# SuperScreen.net
KiCad netlist of a schematic drawn in EAGLE
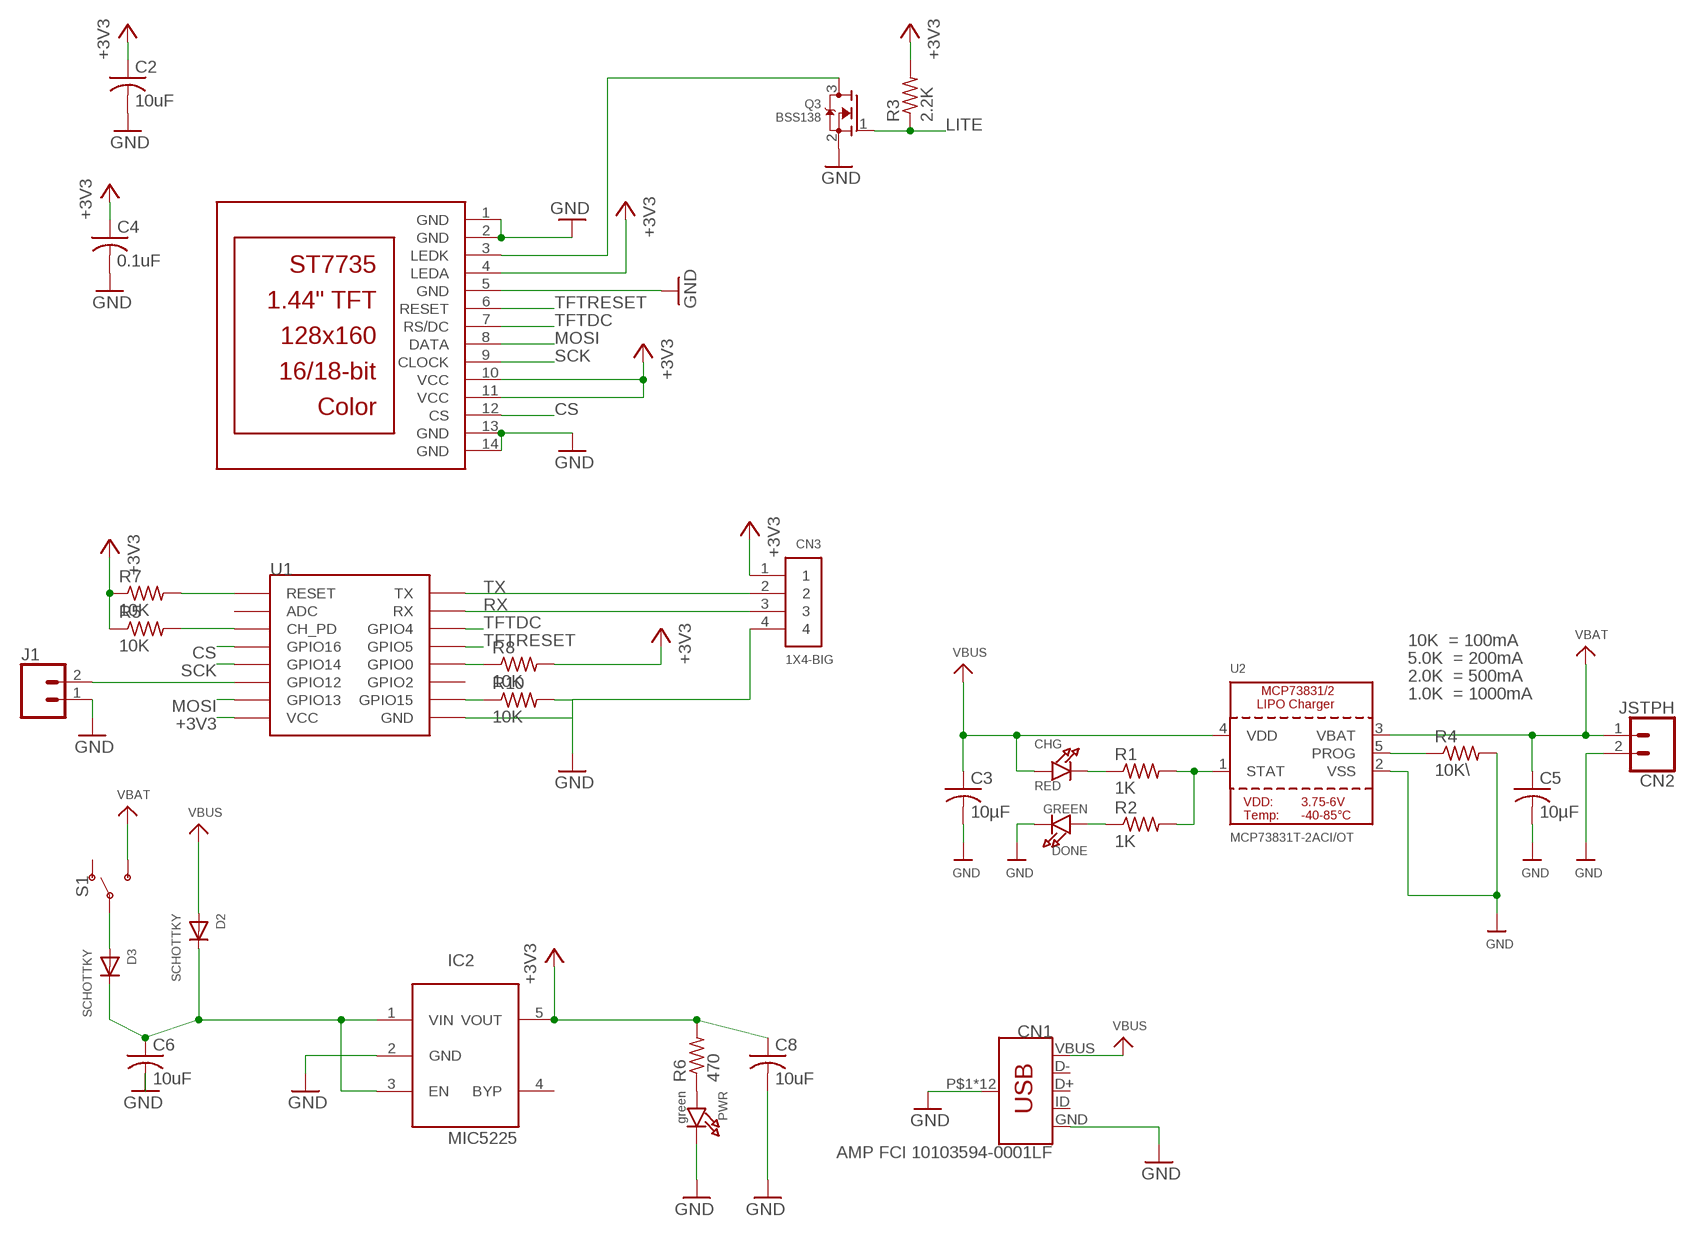
[diagram p0: schematic, sheet 1]

(export (version "E")
  (design (tool "Eeschema 10.0.6"))
  (components
    (comp (ref "C2")
      (value "10uF")
      (footprint "eagle-import:C0805")
      (libsource (lib "eagle-import") (part "C-USC0805"))
    )
    (comp (ref "C3")
      (value "10µF")
      (footprint "eagle-import:C0805")
      (libsource (lib "eagle-import") (part "C-USC0805"))
    )
    (comp (ref "C4")
      (value "0.1uF")
      (footprint "eagle-import:C0805")
      (libsource (lib "eagle-import") (part "C-USC0805"))
    )
    (comp (ref "C5")
      (value "10µF")
      (footprint "eagle-import:C0805")
      (libsource (lib "eagle-import") (part "C-USC0805"))
    )
    (comp (ref "C6")
      (value "10uF")
      (footprint "eagle-import:C0805")
      (libsource (lib "eagle-import") (part "C-USC0805"))
    )
    (comp (ref "C8")
      (value "10uF")
      (footprint "eagle-import:C0805")
      (libsource (lib "eagle-import") (part "C-USC0805"))
    )
    (comp (ref "CHG")
      (value "RED")
      (footprint "eagle-import:CHIPLED_0805_NOOUTLINE")
      (libsource (lib "eagle-import") (part "LED0805_NOOUTLINE"))
    )
    (comp (ref "CN1")
      (value "AMP FCI 10103594-0001LF")
      (footprint "eagle-import:USB-MICROB-PTH")
      (libsource (lib "eagle-import") (part "USB_MICRO-B_HALF_PTH"))
    )
    (comp (ref "CN2")
      (value "JSTPH")
      (footprint "eagle-import:1X02")
      (libsource (lib "eagle-import") (part "CONN_02"))
    )
    (comp (ref "CN3")
      (value "1X4-BIG")
      (footprint "eagle-import:1X04-BIG")
      (libsource (lib "eagle-import") (part "1X4-BIG"))
    )
    (comp (ref "D2")
      (value "SCHOTTKY")
      (footprint "eagle-import:SOD-123FL")
      (libsource (lib "eagle-import") (part "DIODE_SOD-123FL"))
    )
    (comp (ref "D3")
      (value "SCHOTTKY")
      (footprint "eagle-import:SOD-123FL")
      (libsource (lib "eagle-import") (part "DIODE_SOD-123FL"))
    )
    (comp (ref "DONE")
      (value "GREEN")
      (footprint "eagle-import:CHIPLED_0805_NOOUTLINE")
      (libsource (lib "eagle-import") (part "LED0805_NOOUTLINE"))
    )
    (comp (ref "IC2")
      (value "MIC5225")
      (footprint "eagle-import:SOT23-5L")
      (libsource (lib "eagle-import") (part "LP298XS"))
    )
    (comp (ref "J1")
      (value "CONN_02")
      (footprint "eagle-import:1X02")
      (libsource (lib "eagle-import") (part "CONN_02"))
    )
    (comp (ref "PWR")
      (value "green")
      (footprint "eagle-import:CHIPLED_0805_NOOUTLINE")
      (libsource (lib "eagle-import") (part "LED0805_NOOUTLINE"))
    )
    (comp (ref "Q3")
      (value "BSS138")
      (footprint "eagle-import:SOT23-WIDE")
      (libsource (lib "eagle-import") (part "MOSFET-NWIDE"))
    )
    (comp (ref "R1")
      (value "1K")
      (footprint "eagle-import:R0805")
      (libsource (lib "eagle-import") (part "R-US_R0805"))
    )
    (comp (ref "R2")
      (value "1K")
      (footprint "eagle-import:R0805")
      (libsource (lib "eagle-import") (part "R-US_R0805"))
    )
    (comp (ref "R3")
      (value "2.2K")
      (footprint "eagle-import:R0805")
      (libsource (lib "eagle-import") (part "R-US_R0805"))
    )
    (comp (ref "R4")
      (value "10K\\")
      (footprint "eagle-import:R0805")
      (libsource (lib "eagle-import") (part "R-US_R0805"))
    )
    (comp (ref "R5")
      (value "10K")
      (footprint "eagle-import:R0805")
      (libsource (lib "eagle-import") (part "R-US_R0805"))
    )
    (comp (ref "R6")
      (value "470")
      (footprint "eagle-import:R0805")
      (libsource (lib "eagle-import") (part "R-US_R0805"))
    )
    (comp (ref "R7")
      (value "10K")
      (footprint "eagle-import:R0805")
      (libsource (lib "eagle-import") (part "R-US_R0805"))
    )
    (comp (ref "R8")
      (value "10K")
      (footprint "eagle-import:R0805")
      (libsource (lib "eagle-import") (part "R-US_R0805"))
    )
    (comp (ref "R10")
      (value "10K")
      (footprint "eagle-import:R0805")
      (libsource (lib "eagle-import") (part "R-US_R0805"))
    )
    (comp (ref "S1")
      (value "SWITCH-SPDT-SMD-RIGHT-ANGLE")
      (footprint "eagle-import:SWITCH_SPST_SMD_A")
      (libsource (lib "eagle-import") (part "SWITCH-SPDT-SMD-RIGHT-ANGLE"))
    )
    (comp (ref "TFT2")
      (value "DISP_LCD_ST7735_1.44IN")
      (footprint "eagle-import:TFT_1.44IN_128_128")
      (libsource (lib "eagle-import") (part "DISP_LCD_ST7735_1.44IN"))
    )
    (comp (ref "U1")
      (value "ESP12SMD")
      (footprint "eagle-import:ESP12-SMD")
      (libsource (lib "eagle-import") (part "ESP12SMD"))
    )
    (comp (ref "U2")
      (value "MCP73831T-2ACI/OT")
      (footprint "eagle-import:SOT23-5")
      (libsource (lib "eagle-import") (part "MCP73831/2"))
    )
  )
  (nets
    (net (code "1") (name "+3V3") (class "Default")
      (node (ref "C2") (pin "1") (pinfunction "1_1") (pintype "passive"))
      (node (ref "C4") (pin "1") (pinfunction "1_1") (pintype "passive"))
      (node (ref "C8") (pin "1") (pinfunction "1_1") (pintype "passive"))
      (node (ref "CN3") (pin "1") (pinfunction "1_1") (pintype "bidirectional"))
      (node (ref "IC2") (pin "5") (pinfunction "VOUT_5") (pintype "bidirectional"))
      (node (ref "R3") (pin "2") (pinfunction "2_2") (pintype "passive"))
      (node (ref "R5") (pin "1") (pinfunction "1_1") (pintype "passive"))
      (node (ref "R6") (pin "2") (pinfunction "2_2") (pintype "passive"))
      (node (ref "R7") (pin "1") (pinfunction "1_1") (pintype "passive"))
      (node (ref "R8") (pin "2") (pinfunction "2_2") (pintype "passive"))
      (node (ref "TFT2") (pin "10") (pinfunction "VCC_10") (pintype "power_in"))
      (node (ref "TFT2") (pin "11") (pinfunction "VCC_11") (pintype "power_in"))
      (node (ref "TFT2") (pin "4") (pinfunction "LEDA_4") (pintype "input"))
      (node (ref "U1") (pin "VCC") (pinfunction "VCC_VCC") (pintype "bidirectional"))
    )
    (net (code "2") (name "/CS") (class "Default")
      (node (ref "TFT2") (pin "12") (pinfunction "CS_12") (pintype "input"))
      (node (ref "U1") (pin "GPIO16") (pinfunction "GPIO16_GPIO16") (pintype "bidirectional"))
    )
    (net (code "3") (name "/LITE") (class "Default")
      (node (ref "Q3") (pin "1") (pinfunction "G_1") (pintype "bidirectional"))
      (node (ref "R3") (pin "1") (pinfunction "1_1") (pintype "passive"))
    )
    (net (code "4") (name "/MOSI") (class "Default")
      (node (ref "TFT2") (pin "8") (pinfunction "DATA_8") (pintype "bidirectional"))
      (node (ref "U1") (pin "GPIO13") (pinfunction "GPIO13_GPIO13") (pintype "bidirectional"))
    )
    (net (code "5") (name "/RX") (class "Default")
      (node (ref "CN3") (pin "3") (pinfunction "3_3") (pintype "bidirectional"))
      (node (ref "U1") (pin "RXD0") (pinfunction "RX_RXD0") (pintype "bidirectional"))
    )
    (net (code "6") (name "/SCK") (class "Default")
      (node (ref "TFT2") (pin "9") (pinfunction "CLOCK_9") (pintype "input"))
      (node (ref "U1") (pin "GPIO14") (pinfunction "GPIO14_GPIO14") (pintype "bidirectional"))
    )
    (net (code "7") (name "/TFTDC") (class "Default")
      (node (ref "TFT2") (pin "7") (pinfunction "RS/DC_7") (pintype "input"))
      (node (ref "U1") (pin "GPIO4") (pinfunction "GPIO4_GPIO4") (pintype "bidirectional"))
    )
    (net (code "8") (name "/TFTRESET") (class "Default")
      (node (ref "TFT2") (pin "6") (pinfunction "RESET_6") (pintype "input"))
      (node (ref "U1") (pin "GPIO5") (pinfunction "GPIO5_GPIO5") (pintype "bidirectional"))
    )
    (net (code "9") (name "/TX") (class "Default")
      (node (ref "CN3") (pin "2") (pinfunction "2_2") (pintype "bidirectional"))
      (node (ref "U1") (pin "TXD0") (pinfunction "TX_TXD0") (pintype "bidirectional"))
    )
    (net (code "10") (name "GND") (class "Default")
      (node (ref "C2") (pin "2") (pinfunction "2_2") (pintype "passive"))
      (node (ref "C3") (pin "2") (pinfunction "2_2") (pintype "passive"))
      (node (ref "C4") (pin "2") (pinfunction "2_2") (pintype "passive"))
      (node (ref "C5") (pin "2") (pinfunction "2_2") (pintype "passive"))
      (node (ref "C6") (pin "2") (pinfunction "2_2") (pintype "passive"))
      (node (ref "C8") (pin "2") (pinfunction "2_2") (pintype "passive"))
      (node (ref "CN1") (pin "GND") (pinfunction "GND_GND") (pintype "power_in"))
      (node (ref "CN1") (pin "P$1") (pinfunction "SHIELD_P$1") (pintype "bidirectional"))
      (node (ref "CN1") (pin "P$10") (pinfunction "SHIELD_P$10") (pintype "bidirectional"))
      (node (ref "CN1") (pin "P$12") (pinfunction "SHIELD_P$12") (pintype "bidirectional"))
      (node (ref "CN1") (pin "P$2") (pinfunction "SHIELD_P$2") (pintype "bidirectional"))
      (node (ref "CN1") (pin "P$3") (pinfunction "SHIELD_P$3") (pintype "bidirectional"))
      (node (ref "CN1") (pin "P$4") (pinfunction "SHIELD_P$4") (pintype "bidirectional"))
      (node (ref "CN1") (pin "P$6") (pinfunction "SHIELD_P$6") (pintype "bidirectional"))
      (node (ref "CN1") (pin "P$8") (pinfunction "SHIELD_P$8") (pintype "bidirectional"))
      (node (ref "CN1") (pin "SHEILD2") (pinfunction "SHIELD_SHEILD2") (pintype "bidirectional"))
      (node (ref "CN1") (pin "SHIELD") (pinfunction "SHIELD_SHIELD") (pintype "bidirectional"))
      (node (ref "CN1") (pin "SHIELD3") (pinfunction "SHIELD_SHIELD3") (pintype "bidirectional"))
      (node (ref "CN1") (pin "SHIELD4") (pinfunction "SHIELD_SHIELD4") (pintype "bidirectional"))
      (node (ref "CN2") (pin "2") (pinfunction "2_2") (pintype "passive"))
      (node (ref "CN3") (pin "4") (pinfunction "4_4") (pintype "bidirectional"))
      (node (ref "DONE") (pin "C") (pinfunction "C_C") (pintype "passive"))
      (node (ref "IC2") (pin "2") (pinfunction "GND_2") (pintype "bidirectional"))
      (node (ref "J1") (pin "1") (pinfunction "1_1") (pintype "passive"))
      (node (ref "PWR") (pin "C") (pinfunction "C_C") (pintype "passive"))
      (node (ref "Q3") (pin "2") (pinfunction "S_2") (pintype "bidirectional"))
      (node (ref "R10") (pin "2") (pinfunction "2_2") (pintype "passive"))
      (node (ref "R4") (pin "2") (pinfunction "2_2") (pintype "passive"))
      (node (ref "TFT2") (pin "1") (pinfunction "GND_1") (pintype "power_in"))
      (node (ref "TFT2") (pin "13") (pinfunction "GND_13") (pintype "power_in"))
      (node (ref "TFT2") (pin "14") (pinfunction "GND_14") (pintype "power_in"))
      (node (ref "TFT2") (pin "2") (pinfunction "GND_2") (pintype "power_in"))
      (node (ref "TFT2") (pin "5") (pinfunction "GND_5") (pintype "power_in"))
      (node (ref "U1") (pin "GND") (pinfunction "GND_GND") (pintype "bidirectional"))
      (node (ref "U2") (pin "2") (pinfunction "VSS_2") (pintype "power_in"))
    )
    (net (code "11") (name "Net-(CHG-PadC)") (class "Default")
      (node (ref "CHG") (pin "C") (pinfunction "C_C") (pintype "passive"))
      (node (ref "R1") (pin "1") (pinfunction "1_1") (pintype "passive"))
    )
    (net (code "12") (name "Net-(DONE-PadA)") (class "Default")
      (node (ref "DONE") (pin "A") (pinfunction "A_A") (pintype "passive"))
      (node (ref "R2") (pin "1") (pinfunction "1_1") (pintype "passive"))
    )
    (net (code "13") (name "Net-(IC2-EN)") (class "Default")
      (node (ref "C6") (pin "1") (pinfunction "1_1") (pintype "passive"))
      (node (ref "D2") (pin "C") (pinfunction "C_C") (pintype "passive"))
      (node (ref "D3") (pin "C") (pinfunction "C_C") (pintype "passive"))
      (node (ref "IC2") (pin "1") (pinfunction "VIN_1") (pintype "bidirectional"))
      (node (ref "IC2") (pin "3") (pinfunction "EN_3") (pintype "bidirectional"))
    )
    (net (code "14") (name "Net-(J1-Pad2)") (class "Default")
      (node (ref "J1") (pin "2") (pinfunction "2_2") (pintype "passive"))
      (node (ref "U1") (pin "GPIO12") (pinfunction "GPIO12_GPIO12") (pintype "bidirectional"))
    )
    (net (code "15") (name "Net-(PWR-PadA)") (class "Default")
      (node (ref "PWR") (pin "A") (pinfunction "A_A") (pintype "passive"))
      (node (ref "R6") (pin "1") (pinfunction "1_1") (pintype "passive"))
    )
    (net (code "16") (name "Net-(Q3-D)") (class "Default")
      (node (ref "Q3") (pin "3") (pinfunction "D_3") (pintype "bidirectional"))
      (node (ref "TFT2") (pin "3") (pinfunction "LEDK_3") (pintype "input"))
    )
    (net (code "17") (name "Net-(R5-Pad2)") (class "Default")
      (node (ref "R5") (pin "2") (pinfunction "2_2") (pintype "passive"))
      (node (ref "U1") (pin "CH_PD") (pinfunction "CH_PD_CH_PD") (pintype "bidirectional"))
    )
    (net (code "18") (name "Net-(R7-Pad2)") (class "Default")
      (node (ref "R7") (pin "2") (pinfunction "2_2") (pintype "passive"))
      (node (ref "U1") (pin "RESET") (pinfunction "RESET_RESET") (pintype "bidirectional"))
    )
    (net (code "19") (name "Net-(R8-Pad1)") (class "Default")
      (node (ref "R8") (pin "1") (pinfunction "1_1") (pintype "passive"))
      (node (ref "U1") (pin "GPIO0") (pinfunction "GPIO0_GPIO0") (pintype "bidirectional"))
    )
    (net (code "20") (name "Net-(R10-Pad1)") (class "Default")
      (node (ref "R10") (pin "1") (pinfunction "1_1") (pintype "passive"))
      (node (ref "U1") (pin "GPIO15") (pinfunction "GPIO15_GPIO15") (pintype "bidirectional"))
    )
    (net (code "21") (name "Net-(S1-P)") (class "Default")
      (node (ref "D3") (pin "A") (pinfunction "A_A") (pintype "passive"))
      (node (ref "S1") (pin "2") (pinfunction "P_2") (pintype "passive"))
    )
    (net (code "22") (name "Net-(U2-PROG)") (class "Default")
      (node (ref "R4") (pin "1") (pinfunction "1_1") (pintype "passive"))
      (node (ref "U2") (pin "5") (pinfunction "PROG_5") (pintype "input"))
    )
    (net (code "23") (name "Net-(U2-STAT)") (class "Default")
      (node (ref "R1") (pin "2") (pinfunction "2_2") (pintype "passive"))
      (node (ref "R2") (pin "2") (pinfunction "2_2") (pintype "passive"))
      (node (ref "U2") (pin "1") (pinfunction "STAT_1") (pintype "output"))
    )
    (net (code "24") (name "VBAT") (class "Default")
      (node (ref "C5") (pin "1") (pinfunction "1_1") (pintype "passive"))
      (node (ref "CN2") (pin "1") (pinfunction "1_1") (pintype "passive"))
      (node (ref "S1") (pin "3") (pinfunction "S_3") (pintype "passive"))
      (node (ref "U2") (pin "3") (pinfunction "VBAT_3") (pintype "power_in"))
    )
    (net (code "25") (name "VBUS") (class "Default")
      (node (ref "C3") (pin "1") (pinfunction "1_1") (pintype "passive"))
      (node (ref "CHG") (pin "A") (pinfunction "A_A") (pintype "passive"))
      (node (ref "CN1") (pin "VBUS") (pinfunction "VBUS_VBUS") (pintype "power_in"))
      (node (ref "D2") (pin "A") (pinfunction "A_A") (pintype "passive"))
      (node (ref "U2") (pin "4") (pinfunction "VDD_4") (pintype "power_in"))
    )
    (net (code "26") (name "unconnected-(CN1-PadD+)") (class "Default")
      (node (ref "CN1") (pin "D+") (pinfunction "D+_D+") (pintype "bidirectional"))
    )
    (net (code "27") (name "unconnected-(CN1-PadD-)") (class "Default")
      (node (ref "CN1") (pin "D-") (pinfunction "D-_D-") (pintype "bidirectional"))
    )
    (net (code "28") (name "unconnected-(CN1-PadID)") (class "Default")
      (node (ref "CN1") (pin "ID") (pinfunction "ID_ID") (pintype "bidirectional"))
    )
    (net (code "29") (name "unconnected-(IC2-BYP-Pad4)") (class "Default")
      (node (ref "IC2") (pin "4") (pinfunction "BYP_4") (pintype "bidirectional"))
    )
    (net (code "30") (name "unconnected-(S1-O-Pad1)") (class "Default")
      (node (ref "S1") (pin "1") (pinfunction "O_1") (pintype "passive"))
    )
    (net (code "31") (name "unconnected-(U1-PadADC)") (class "Default")
      (node (ref "U1") (pin "ADC") (pinfunction "ADC_ADC") (pintype "bidirectional"))
    )
    (net (code "32") (name "unconnected-(U1-PadGPIO2)") (class "Default")
      (node (ref "U1") (pin "GPIO2") (pinfunction "GPIO2_GPIO2") (pintype "bidirectional"))
    )
  )
)
